# esp32_component.net
KiCad netlist of a schematic drawn in EAGLE
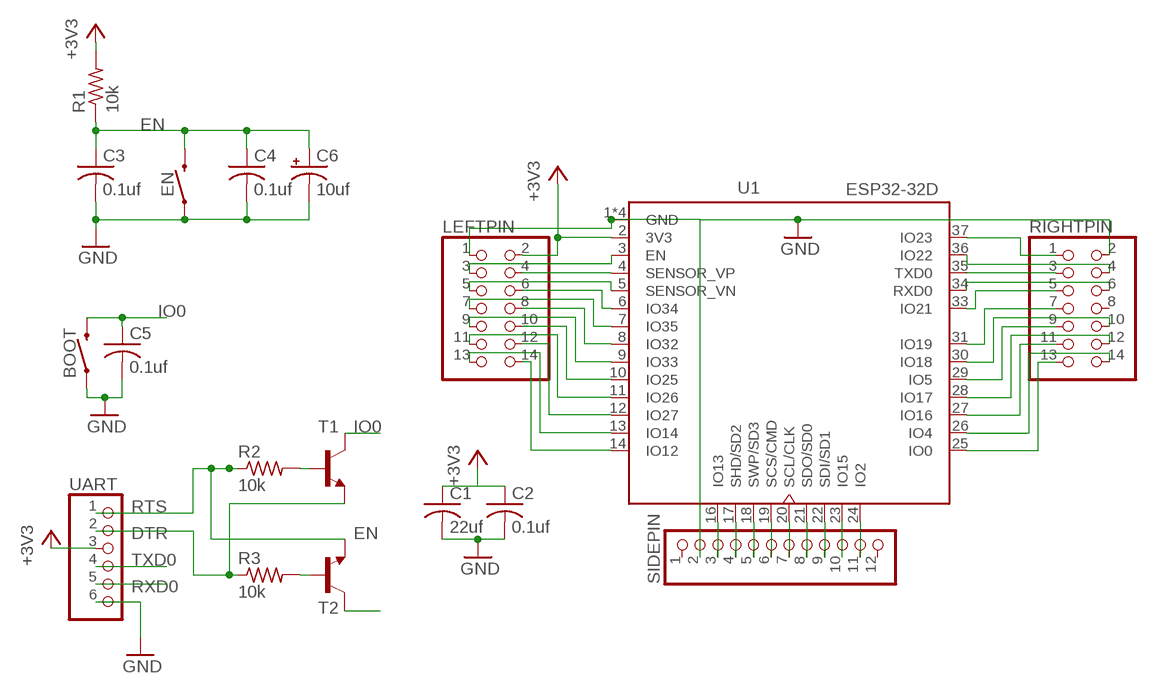
[diagram p0: schematic, sheet 1]

(export (version "E")
  (design (tool "Eeschema 10.0.6"))
  (components
    (comp (ref "BOOT")
      (value "MOMENTARY-SWITCH-SPST-SMD-4.6X2.8MM")
      (footprint "eagle-import:TACTILE_SWITCH_SMD_4.6X2.8MM")
      (libsource (lib "eagle-import") (part "MOMENTARY-SWITCH-SPST-SMD-4.6X2.8MM"))
    )
    (comp (ref "C1")
      (value "22uf")
      (footprint "eagle-import:C1210")
      (libsource (lib "eagle-import") (part "C-USC1210"))
    )
    (comp (ref "C2")
      (value "0.1uf")
      (footprint "eagle-import:C0805")
      (libsource (lib "eagle-import") (part "C-USC0805"))
    )
    (comp (ref "C3")
      (value "0.1uf")
      (footprint "eagle-import:C0805")
      (libsource (lib "eagle-import") (part "C-USC0805"))
    )
    (comp (ref "C4")
      (value "0.1uf")
      (footprint "eagle-import:C0805")
      (libsource (lib "eagle-import") (part "C-USC0805"))
    )
    (comp (ref "C5")
      (value "0.1uf")
      (footprint "eagle-import:C0805")
      (libsource (lib "eagle-import") (part "C-USC0805"))
    )
    (comp (ref "C6")
      (value "10uf")
      (footprint "eagle-import:153CLV-0605")
      (libsource (lib "eagle-import") (part "CPOL-US153CLV-0605"))
    )
    (comp (ref "EN")
      (value "MOMENTARY-SWITCH-SPST-SMD-4.6X2.8MM")
      (footprint "eagle-import:TACTILE_SWITCH_SMD_4.6X2.8MM")
      (libsource (lib "eagle-import") (part "MOMENTARY-SWITCH-SPST-SMD-4.6X2.8MM"))
    )
    (comp (ref "LEFTPIN")
      (value "PINHD-2X7")
      (footprint "eagle-import:2X07")
      (libsource (lib "eagle-import") (part "PINHD-2X7"))
    )
    (comp (ref "R1")
      (value "10k")
      (footprint "eagle-import:R0805")
      (libsource (lib "eagle-import") (part "R-US_R0805"))
    )
    (comp (ref "R2")
      (value "10k")
      (footprint "eagle-import:M0805")
      (libsource (lib "eagle-import") (part "R-US_M0805"))
    )
    (comp (ref "R3")
      (value "10k")
      (footprint "eagle-import:M0805")
      (libsource (lib "eagle-import") (part "R-US_M0805"))
    )
    (comp (ref "RIGHTPIN")
      (value "PINHD-2X7")
      (footprint "eagle-import:2X07")
      (libsource (lib "eagle-import") (part "PINHD-2X7"))
    )
    (comp (ref "SIDEPIN")
      (value "PINHD-1X12")
      (footprint "eagle-import:1X12")
      (libsource (lib "eagle-import") (part "PINHD-1X12"))
    )
    (comp (ref "T1")
      (value "-NPN-SOT23-EBC")
      (footprint "eagle-import:SOT23-EBC")
      (libsource (lib "eagle-import") (part "-NPN-SOT23-EBC"))
    )
    (comp (ref "T2")
      (value "-NPN-SOT23-EBC")
      (footprint "eagle-import:SOT23-EBC")
      (libsource (lib "eagle-import") (part "-NPN-SOT23-EBC"))
    )
    (comp (ref "U1")
      (value "ESP32-32D")
      (footprint "eagle-import:MODULE_ESP32-WROOM-32D")
      (fields (field (name "MF") "Espressif Systems") (field (name "MP") "ESP32-WROOM-32D"))
      (libsource (lib "eagle-import") (part "ESP32-32D"))
    )
    (comp (ref "UART")
      (value "PINHD-1X6")
      (footprint "eagle-import:1X06")
      (libsource (lib "eagle-import") (part "PINHD-1X6"))
    )
  )
  (nets
    (net (code "1") (name "+3V3") (class "Default")
      (node (ref "C1") (pin "1") (pinfunction "1_1") (pintype "passive"))
      (node (ref "C2") (pin "1") (pinfunction "1_1") (pintype "passive"))
      (node (ref "LEFTPIN") (pin "2") (pinfunction "2_2") (pintype "passive"))
      (node (ref "R1") (pin "2") (pinfunction "2_2") (pintype "passive"))
      (node (ref "U1") (pin "2") (pinfunction "3V3_2") (pintype "power_in"))
      (node (ref "UART") (pin "3") (pinfunction "3_3") (pintype "passive"))
    )
    (net (code "2") (name "/DTR") (class "Default")
      (node (ref "R3") (pin "1") (pinfunction "1_1") (pintype "passive"))
      (node (ref "T1") (pin "E") (pinfunction "E_E") (pintype "passive"))
      (node (ref "UART") (pin "2") (pinfunction "2_2") (pintype "passive"))
    )
    (net (code "3") (name "/EN") (class "Default")
      (node (ref "C3") (pin "1") (pinfunction "1_1") (pintype "passive"))
      (node (ref "C4") (pin "1") (pinfunction "1_1") (pintype "passive"))
      (node (ref "C6") (pin "+") (pinfunction "+_+") (pintype "passive"))
      (node (ref "EN") (pin "3") (pinfunction "2_3") (pintype "passive"))
      (node (ref "EN") (pin "4") (pinfunction "2_4") (pintype "passive"))
      (node (ref "LEFTPIN") (pin "3") (pinfunction "3_3") (pintype "passive"))
      (node (ref "R1") (pin "1") (pinfunction "1_1") (pintype "passive"))
      (node (ref "T2") (pin "C") (pinfunction "C_C") (pintype "passive"))
      (node (ref "U1") (pin "3") (pinfunction "EN_3") (pintype "input"))
    )
    (net (code "4") (name "/IO0") (class "Default")
      (node (ref "BOOT") (pin "3") (pinfunction "2_3") (pintype "passive"))
      (node (ref "BOOT") (pin "4") (pinfunction "2_4") (pintype "passive"))
      (node (ref "C5") (pin "1") (pinfunction "1_1") (pintype "passive"))
      (node (ref "RIGHTPIN") (pin "13") (pinfunction "13_13") (pintype "passive"))
      (node (ref "T1") (pin "C") (pinfunction "C_C") (pintype "passive"))
      (node (ref "U1") (pin "25") (pinfunction "IO0_25") (pintype "bidirectional"))
    )
    (net (code "5") (name "/RTS") (class "Default")
      (node (ref "R2") (pin "1") (pinfunction "1_1") (pintype "passive"))
      (node (ref "T2") (pin "E") (pinfunction "E_E") (pintype "passive"))
      (node (ref "UART") (pin "1") (pinfunction "1_1") (pintype "passive"))
    )
    (net (code "6") (name "/RXD0") (class "Default")
      (node (ref "RIGHTPIN") (pin "6") (pinfunction "6_6") (pintype "passive"))
      (node (ref "U1") (pin "34") (pinfunction "RXD0_34") (pintype "bidirectional"))
      (node (ref "UART") (pin "5") (pinfunction "5_5") (pintype "passive"))
    )
    (net (code "7") (name "/TXD0") (class "Default")
      (node (ref "RIGHTPIN") (pin "3") (pinfunction "3_3") (pintype "passive"))
      (node (ref "U1") (pin "35") (pinfunction "TXD0_35") (pintype "bidirectional"))
      (node (ref "UART") (pin "4") (pinfunction "4_4") (pintype "passive"))
    )
    (net (code "8") (name "GND") (class "Default")
      (node (ref "BOOT") (pin "1") (pinfunction "1_1") (pintype "passive"))
      (node (ref "BOOT") (pin "2") (pinfunction "1_2") (pintype "passive"))
      (node (ref "C1") (pin "2") (pinfunction "2_2") (pintype "passive"))
      (node (ref "C2") (pin "2") (pinfunction "2_2") (pintype "passive"))
      (node (ref "C3") (pin "2") (pinfunction "2_2") (pintype "passive"))
      (node (ref "C4") (pin "2") (pinfunction "2_2") (pintype "passive"))
      (node (ref "C5") (pin "2") (pinfunction "2_2") (pintype "passive"))
      (node (ref "C6") (pin "-") (pinfunction "-_-") (pintype "passive"))
      (node (ref "EN") (pin "1") (pinfunction "1_1") (pintype "passive"))
      (node (ref "EN") (pin "2") (pinfunction "1_2") (pintype "passive"))
      (node (ref "LEFTPIN") (pin "1") (pinfunction "1_1") (pintype "passive"))
      (node (ref "RIGHTPIN") (pin "2") (pinfunction "2_2") (pintype "passive"))
      (node (ref "SIDEPIN") (pin "2") (pinfunction "2_2") (pintype "passive"))
      (node (ref "U1") (pin "1") (pinfunction "GND_1") (pintype "power_in"))
      (node (ref "U1") (pin "15") (pinfunction "GND_15") (pintype "power_in"))
      (node (ref "U1") (pin "38") (pinfunction "GND_38") (pintype "power_in"))
      (node (ref "U1") (pin "39") (pinfunction "GND_39") (pintype "power_in"))
      (node (ref "UART") (pin "6") (pinfunction "6_6") (pintype "passive"))
    )
    (net (code "9") (name "Net-(R2-Pad2)") (class "Default")
      (node (ref "R2") (pin "2") (pinfunction "2_2") (pintype "passive"))
      (node (ref "T1") (pin "B") (pinfunction "B_B") (pintype "passive"))
    )
    (net (code "10") (name "Net-(R3-Pad2)") (class "Default")
      (node (ref "R3") (pin "2") (pinfunction "2_2") (pintype "passive"))
      (node (ref "T2") (pin "B") (pinfunction "B_B") (pintype "passive"))
    )
    (net (code "11") (name "Net-(U1-IO2)") (class "Default")
      (node (ref "SIDEPIN") (pin "11") (pinfunction "11_11") (pintype "passive"))
      (node (ref "U1") (pin "24") (pinfunction "IO2_24") (pintype "bidirectional"))
    )
    (net (code "12") (name "Net-(U1-IO4)") (class "Default")
      (node (ref "RIGHTPIN") (pin "14") (pinfunction "14_14") (pintype "passive"))
      (node (ref "U1") (pin "26") (pinfunction "IO4_26") (pintype "bidirectional"))
    )
    (net (code "13") (name "Net-(U1-IO5)") (class "Default")
      (node (ref "RIGHTPIN") (pin "9") (pinfunction "9_9") (pintype "passive"))
      (node (ref "U1") (pin "29") (pinfunction "IO5_29") (pintype "bidirectional"))
    )
    (net (code "14") (name "Net-(U1-IO12)") (class "Default")
      (node (ref "LEFTPIN") (pin "14") (pinfunction "14_14") (pintype "passive"))
      (node (ref "U1") (pin "14") (pinfunction "IO12_14") (pintype "bidirectional"))
    )
    (net (code "15") (name "Net-(U1-IO13)") (class "Default")
      (node (ref "SIDEPIN") (pin "3") (pinfunction "3_3") (pintype "passive"))
      (node (ref "U1") (pin "16") (pinfunction "IO13_16") (pintype "bidirectional"))
    )
    (net (code "16") (name "Net-(U1-IO14)") (class "Default")
      (node (ref "LEFTPIN") (pin "13") (pinfunction "13_13") (pintype "passive"))
      (node (ref "U1") (pin "13") (pinfunction "IO14_13") (pintype "bidirectional"))
    )
    (net (code "17") (name "Net-(U1-IO15)") (class "Default")
      (node (ref "SIDEPIN") (pin "10") (pinfunction "10_10") (pintype "passive"))
      (node (ref "U1") (pin "23") (pinfunction "IO15_23") (pintype "bidirectional"))
    )
    (net (code "18") (name "Net-(U1-IO16)") (class "Default")
      (node (ref "RIGHTPIN") (pin "11") (pinfunction "11_11") (pintype "passive"))
      (node (ref "U1") (pin "27") (pinfunction "IO16_27") (pintype "bidirectional"))
    )
    (net (code "19") (name "Net-(U1-IO17)") (class "Default")
      (node (ref "RIGHTPIN") (pin "12") (pinfunction "12_12") (pintype "passive"))
      (node (ref "U1") (pin "28") (pinfunction "IO17_28") (pintype "bidirectional"))
    )
    (net (code "20") (name "Net-(U1-IO18)") (class "Default")
      (node (ref "RIGHTPIN") (pin "10") (pinfunction "10_10") (pintype "passive"))
      (node (ref "U1") (pin "30") (pinfunction "IO18_30") (pintype "bidirectional"))
    )
    (net (code "21") (name "Net-(U1-IO19)") (class "Default")
      (node (ref "RIGHTPIN") (pin "7") (pinfunction "7_7") (pintype "passive"))
      (node (ref "U1") (pin "31") (pinfunction "IO19_31") (pintype "bidirectional"))
    )
    (net (code "22") (name "Net-(U1-IO21)") (class "Default")
      (node (ref "RIGHTPIN") (pin "5") (pinfunction "5_5") (pintype "passive"))
      (node (ref "U1") (pin "33") (pinfunction "IO21_33") (pintype "bidirectional"))
    )
    (net (code "23") (name "Net-(U1-IO22)") (class "Default")
      (node (ref "RIGHTPIN") (pin "4") (pinfunction "4_4") (pintype "passive"))
      (node (ref "U1") (pin "36") (pinfunction "IO22_36") (pintype "bidirectional"))
    )
    (net (code "24") (name "Net-(U1-IO23)") (class "Default")
      (node (ref "RIGHTPIN") (pin "1") (pinfunction "1_1") (pintype "passive"))
      (node (ref "U1") (pin "37") (pinfunction "IO23_37") (pintype "bidirectional"))
    )
    (net (code "25") (name "Net-(U1-IO25)") (class "Default")
      (node (ref "LEFTPIN") (pin "10") (pinfunction "10_10") (pintype "passive"))
      (node (ref "U1") (pin "10") (pinfunction "IO25_10") (pintype "bidirectional"))
    )
    (net (code "26") (name "Net-(U1-IO26)") (class "Default")
      (node (ref "LEFTPIN") (pin "11") (pinfunction "11_11") (pintype "passive"))
      (node (ref "U1") (pin "11") (pinfunction "IO26_11") (pintype "bidirectional"))
    )
    (net (code "27") (name "Net-(U1-IO27)") (class "Default")
      (node (ref "LEFTPIN") (pin "12") (pinfunction "12_12") (pintype "passive"))
      (node (ref "U1") (pin "12") (pinfunction "IO27_12") (pintype "bidirectional"))
    )
    (net (code "28") (name "Net-(U1-IO32)") (class "Default")
      (node (ref "LEFTPIN") (pin "8") (pinfunction "8_8") (pintype "passive"))
      (node (ref "U1") (pin "8") (pinfunction "IO32_8") (pintype "bidirectional"))
    )
    (net (code "29") (name "Net-(U1-IO33)") (class "Default")
      (node (ref "LEFTPIN") (pin "9") (pinfunction "9_9") (pintype "passive"))
      (node (ref "U1") (pin "9") (pinfunction "IO33_9") (pintype "bidirectional"))
    )
    (net (code "30") (name "Net-(U1-IO34)") (class "Default")
      (node (ref "LEFTPIN") (pin "6") (pinfunction "6_6") (pintype "passive"))
      (node (ref "U1") (pin "6") (pinfunction "IO34_6") (pintype "bidirectional"))
    )
    (net (code "31") (name "Net-(U1-IO35)") (class "Default")
      (node (ref "LEFTPIN") (pin "7") (pinfunction "7_7") (pintype "passive"))
      (node (ref "U1") (pin "7") (pinfunction "IO35_7") (pintype "bidirectional"))
    )
    (net (code "32") (name "Net-(U1-SCL{slash}CLK)") (class "Default")
      (node (ref "SIDEPIN") (pin "7") (pinfunction "7_7") (pintype "passive"))
      (node (ref "U1") (pin "20") (pinfunction "SCL/CLK_20") (pintype "bidirectional"))
    )
    (net (code "33") (name "Net-(U1-SCS{slash}CMD)") (class "Default")
      (node (ref "SIDEPIN") (pin "6") (pinfunction "6_6") (pintype "passive"))
      (node (ref "U1") (pin "19") (pinfunction "SCS/CMD_19") (pintype "bidirectional"))
    )
    (net (code "34") (name "Net-(U1-SDI{slash}SD1)") (class "Default")
      (node (ref "SIDEPIN") (pin "9") (pinfunction "9_9") (pintype "passive"))
      (node (ref "U1") (pin "22") (pinfunction "SDI/SD1_22") (pintype "bidirectional"))
    )
    (net (code "35") (name "Net-(U1-SDO{slash}SD0)") (class "Default")
      (node (ref "SIDEPIN") (pin "8") (pinfunction "8_8") (pintype "passive"))
      (node (ref "U1") (pin "21") (pinfunction "SDO/SD0_21") (pintype "bidirectional"))
    )
    (net (code "36") (name "Net-(U1-SENSOR_VN)") (class "Default")
      (node (ref "LEFTPIN") (pin "5") (pinfunction "5_5") (pintype "passive"))
      (node (ref "U1") (pin "5") (pinfunction "SENSOR_VN_5") (pintype "input"))
    )
    (net (code "37") (name "Net-(U1-SENSOR_VP)") (class "Default")
      (node (ref "LEFTPIN") (pin "4") (pinfunction "4_4") (pintype "passive"))
      (node (ref "U1") (pin "4") (pinfunction "SENSOR_VP_4") (pintype "input"))
    )
    (net (code "38") (name "Net-(U1-SHD{slash}SD2)") (class "Default")
      (node (ref "SIDEPIN") (pin "4") (pinfunction "4_4") (pintype "passive"))
      (node (ref "U1") (pin "17") (pinfunction "SHD/SD2_17") (pintype "bidirectional"))
    )
    (net (code "39") (name "Net-(U1-SWP{slash}SD3)") (class "Default")
      (node (ref "SIDEPIN") (pin "5") (pinfunction "5_5") (pintype "passive"))
      (node (ref "U1") (pin "18") (pinfunction "SWP/SD3_18") (pintype "bidirectional"))
    )
    (net (code "40") (name "unconnected-(RIGHTPIN-Pad8)") (class "Default")
      (node (ref "RIGHTPIN") (pin "8") (pinfunction "8_8") (pintype "passive"))
    )
    (net (code "41") (name "unconnected-(SIDEPIN-Pad1)") (class "Default")
      (node (ref "SIDEPIN") (pin "1") (pinfunction "1_1") (pintype "passive"))
    )
    (net (code "42") (name "unconnected-(SIDEPIN-Pad12)") (class "Default")
      (node (ref "SIDEPIN") (pin "12") (pinfunction "12_12") (pintype "passive"))
    )
  )
)
